# Shield.net
KiCad netlist of a schematic drawn in EAGLE
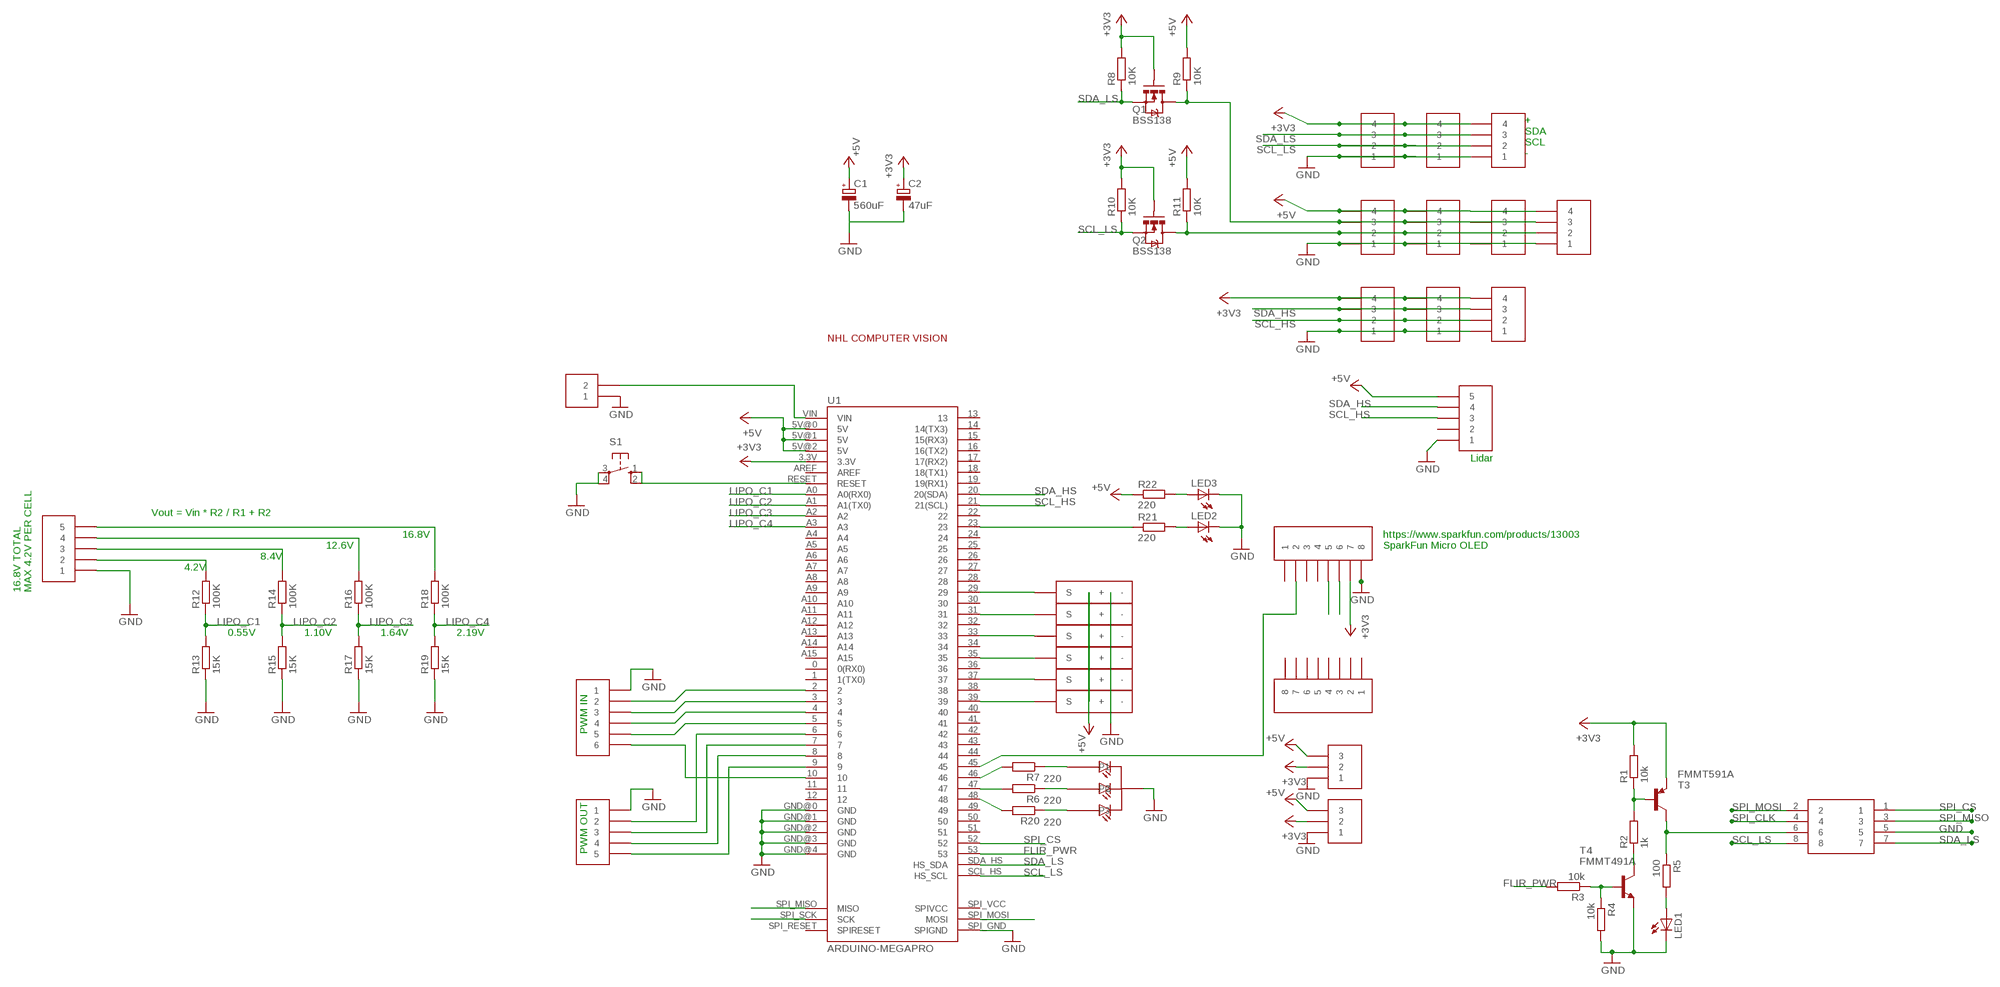
[diagram p0: schematic, sheet 1]

(export (version "E")
  (design (tool "Eeschema 10.0.6"))
  (components
    (comp (ref "C1")
      (value "560uF")
      (footprint "eagle-import:153CLV-1010")
      (libsource (lib "eagle-import") (part "CPOL-EU153CLV-1010"))
    )
    (comp (ref "C2")
      (value "47uF")
      (footprint "eagle-import:153CLV-0605")
      (libsource (lib "eagle-import") (part "CPOL-EU153CLV-0605"))
    )
    (comp (ref "LED1")
      (value "LEDSML0805")
      (footprint "eagle-import:SML0805")
      (libsource (lib "eagle-import") (part "LEDSML0805"))
    )
    (comp (ref "LED2")
      (value "LEDSML0805")
      (footprint "eagle-import:SML0805")
      (libsource (lib "eagle-import") (part "LEDSML0805"))
    )
    (comp (ref "LED3")
      (value "LEDSML0805")
      (footprint "eagle-import:SML0805")
      (libsource (lib "eagle-import") (part "LEDSML0805"))
    )
    (comp (ref "Q1")
      (value "BSS138")
      (footprint "eagle-import:SOT23-3")
      (libsource (lib "eagle-import") (part "MOSFET-NCHANNELBSS138"))
    )
    (comp (ref "Q2")
      (value "BSS138")
      (footprint "eagle-import:SOT23-3")
      (libsource (lib "eagle-import") (part "MOSFET-NCHANNELBSS138"))
    )
    (comp (ref "R1")
      (value "10k")
      (footprint "eagle-import:R0805")
      (libsource (lib "eagle-import") (part "R-EU_R0805"))
    )
    (comp (ref "R2")
      (value "1k")
      (footprint "eagle-import:R0805")
      (libsource (lib "eagle-import") (part "R-EU_R0805"))
    )
    (comp (ref "R3")
      (value "10k")
      (footprint "eagle-import:R0805")
      (libsource (lib "eagle-import") (part "R-EU_R0805"))
    )
    (comp (ref "R4")
      (value "10k")
      (footprint "eagle-import:R0805")
      (libsource (lib "eagle-import") (part "R-EU_R0805"))
    )
    (comp (ref "R5")
      (value "100")
      (footprint "eagle-import:R0805")
      (libsource (lib "eagle-import") (part "R-EU_R0805"))
    )
    (comp (ref "R6")
      (value "220")
      (footprint "eagle-import:R0805")
      (libsource (lib "eagle-import") (part "R-EU_R0805"))
    )
    (comp (ref "R7")
      (value "220")
      (footprint "eagle-import:R0805")
      (libsource (lib "eagle-import") (part "R-EU_R0805"))
    )
    (comp (ref "R8")
      (value "10K")
      (footprint "eagle-import:R0805")
      (libsource (lib "eagle-import") (part "R-EU_R0805"))
    )
    (comp (ref "R9")
      (value "10K")
      (footprint "eagle-import:R0805")
      (libsource (lib "eagle-import") (part "R-EU_R0805"))
    )
    (comp (ref "R10")
      (value "10K")
      (footprint "eagle-import:R0805")
      (libsource (lib "eagle-import") (part "R-EU_R0805"))
    )
    (comp (ref "R11")
      (value "10K")
      (footprint "eagle-import:R0805")
      (libsource (lib "eagle-import") (part "R-EU_R0805"))
    )
    (comp (ref "R12")
      (value "100K")
      (footprint "eagle-import:R0805")
      (libsource (lib "eagle-import") (part "R-EU_R0805"))
    )
    (comp (ref "R13")
      (value "15K")
      (footprint "eagle-import:R0805")
      (libsource (lib "eagle-import") (part "R-EU_R0805"))
    )
    (comp (ref "R14")
      (value "100K")
      (footprint "eagle-import:R0805")
      (libsource (lib "eagle-import") (part "R-EU_R0805"))
    )
    (comp (ref "R15")
      (value "15K")
      (footprint "eagle-import:R0805")
      (libsource (lib "eagle-import") (part "R-EU_R0805"))
    )
    (comp (ref "R16")
      (value "100K")
      (footprint "eagle-import:R0805")
      (libsource (lib "eagle-import") (part "R-EU_R0805"))
    )
    (comp (ref "R17")
      (value "15K")
      (footprint "eagle-import:R0805")
      (libsource (lib "eagle-import") (part "R-EU_R0805"))
    )
    (comp (ref "R18")
      (value "100K")
      (footprint "eagle-import:R0805")
      (libsource (lib "eagle-import") (part "R-EU_R0805"))
    )
    (comp (ref "R19")
      (value "15K")
      (footprint "eagle-import:R0805")
      (libsource (lib "eagle-import") (part "R-EU_R0805"))
    )
    (comp (ref "R20")
      (value "220")
      (footprint "eagle-import:R0805")
      (libsource (lib "eagle-import") (part "R-EU_R0805"))
    )
    (comp (ref "R21")
      (value "220")
      (footprint "eagle-import:R0805")
      (libsource (lib "eagle-import") (part "R-EU_R0805"))
    )
    (comp (ref "R22")
      (value "220")
      (footprint "eagle-import:R0805")
      (libsource (lib "eagle-import") (part "R-EU_R0805"))
    )
    (comp (ref "S1")
      (value "10-XX")
      (footprint "eagle-import:B3F-10XX")
      (fields (field (name "MPN") "B3F-1000"))
      (libsource (lib "eagle-import") (part "10-XX"))
    )
    (comp (ref "T3")
      (value "FMMT591A ")
      (footprint "eagle-import:SOT23-BCE")
      (libsource (lib "eagle-import") (part "-PNP-SOT23-BCE"))
    )
    (comp (ref "T4")
      (value "FMMT491A ")
      (footprint "eagle-import:SOT23-BEC")
      (libsource (lib "eagle-import") (part "-NPN-SOT23-BECBC808"))
    )
    (comp (ref "U$1")
      (value "RGB5MMRGB5MM")
      (footprint "eagle-import:RGB5MM")
      (libsource (lib "eagle-import") (part "RGB5MMRGB5MM"))
    )
    (comp (ref "U$2")
      (value "JST-4")
      (footprint "eagle-import:JST-4")
      (libsource (lib "eagle-import") (part "JST-4"))
    )
    (comp (ref "U$3")
      (value "JST-4")
      (footprint "eagle-import:JST-4")
      (libsource (lib "eagle-import") (part "JST-4"))
    )
    (comp (ref "U$4")
      (value "JST-4")
      (footprint "eagle-import:JST-4")
      (libsource (lib "eagle-import") (part "JST-4"))
    )
    (comp (ref "U$5")
      (value "JST-4")
      (footprint "eagle-import:JST-4")
      (libsource (lib "eagle-import") (part "JST-4"))
    )
    (comp (ref "U$6")
      (value "JST-4")
      (footprint "eagle-import:JST-4")
      (libsource (lib "eagle-import") (part "JST-4"))
    )
    (comp (ref "U$7")
      (value "JST-4")
      (footprint "eagle-import:JST-4")
      (libsource (lib "eagle-import") (part "JST-4"))
    )
    (comp (ref "U$8")
      (value "JST-4")
      (footprint "eagle-import:JST-4")
      (libsource (lib "eagle-import") (part "JST-4"))
    )
    (comp (ref "U$9")
      (value "JST-4")
      (footprint "eagle-import:JST-4")
      (libsource (lib "eagle-import") (part "JST-4"))
    )
    (comp (ref "U$10")
      (value "JST-4")
      (footprint "eagle-import:JST-4")
      (libsource (lib "eagle-import") (part "JST-4"))
    )
    (comp (ref "U$11")
      (value "JST-4")
      (footprint "eagle-import:JST-4")
      (libsource (lib "eagle-import") (part "JST-4"))
    )
    (comp (ref "U$12")
      (value "LIDAR")
      (footprint "eagle-import:JST-5")
      (libsource (lib "eagle-import") (part "JST-5"))
    )
    (comp (ref "U$13")
      (value "LIDAR")
      (footprint "eagle-import:JST-5")
      (libsource (lib "eagle-import") (part "JST-5"))
    )
    (comp (ref "U$14")
      (value "JST-3")
      (footprint "eagle-import:JST-3")
      (libsource (lib "eagle-import") (part "JST-3"))
    )
    (comp (ref "U$15")
      (value "JST-3")
      (footprint "eagle-import:JST-3")
      (libsource (lib "eagle-import") (part "JST-3"))
    )
    (comp (ref "U$16")
      (value "JST-2")
      (footprint "eagle-import:JST-2")
      (libsource (lib "eagle-import") (part "JST-2"))
    )
    (comp (ref "U$17")
      (value "JST-6")
      (footprint "eagle-import:JST-6")
      (libsource (lib "eagle-import") (part "JST-6"))
    )
    (comp (ref "U$18")
      (value "JST-5")
      (footprint "eagle-import:JST-5")
      (libsource (lib "eagle-import") (part "JST-5"))
    )
    (comp (ref "U$19")
      (value "SERVOHEADER")
      (footprint "eagle-import:SERVOHEADER")
      (libsource (lib "eagle-import") (part "SERVOHEADER"))
    )
    (comp (ref "U$20")
      (value "SERVOHEADER")
      (footprint "eagle-import:SERVOHEADER")
      (libsource (lib "eagle-import") (part "SERVOHEADER"))
    )
    (comp (ref "U$21")
      (value "SERVOHEADER")
      (footprint "eagle-import:SERVOHEADER")
      (libsource (lib "eagle-import") (part "SERVOHEADER"))
    )
    (comp (ref "U$22")
      (value "SERVOHEADER")
      (footprint "eagle-import:SERVOHEADER")
      (libsource (lib "eagle-import") (part "SERVOHEADER"))
    )
    (comp (ref "U$23")
      (value "SERVOHEADER")
      (footprint "eagle-import:SERVOHEADER")
      (libsource (lib "eagle-import") (part "SERVOHEADER"))
    )
    (comp (ref "U$24")
      (value "SERVOHEADER")
      (footprint "eagle-import:SERVOHEADER")
      (libsource (lib "eagle-import") (part "SERVOHEADER"))
    )
    (comp (ref "U$25")
      (value "IDC-8WAY")
      (footprint "eagle-import:IDC-8WAY")
      (libsource (lib "eagle-import") (part "IDC-8WAY"))
    )
    (comp (ref "U$26")
      (value "OLEDHEADER")
      (footprint "eagle-import:OLEDHEADER")
      (libsource (lib "eagle-import") (part "OLEDHEADER"))
    )
    (comp (ref "U$27")
      (value "OLEDHEADER")
      (footprint "eagle-import:OLEDHEADER")
      (libsource (lib "eagle-import") (part "OLEDHEADER"))
    )
    (comp (ref "U$28")
      (value "NHLLOGO")
      (footprint "eagle-import:NHLLOGO")
      (libsource (lib "eagle-import") (part "NHLLOGO"))
    )
    (comp (ref "U1")
      (value "ARDUINO-MEGAPRO")
      (footprint "eagle-import:ARDUINO_MEGA-PRO-3.3V")
      (libsource (lib "eagle-import") (part "ARDUINO-MEGAPRO"))
    )
  )
  (nets
    (net (code "1") (name "+3V3") (class "Default")
      (node (ref "C2") (pin "+") (pinfunction "+_+") (pintype "passive"))
      (node (ref "Q1") (pin "1") (pinfunction "G_1") (pintype "passive"))
      (node (ref "Q2") (pin "1") (pinfunction "G_1") (pintype "passive"))
      (node (ref "R1") (pin "2") (pinfunction "2_2") (pintype "passive"))
      (node (ref "R10") (pin "2") (pinfunction "2_2") (pintype "passive"))
      (node (ref "R8") (pin "2") (pinfunction "2_2") (pintype "passive"))
      (node (ref "T3") (pin "E") (pinfunction "E_E") (pintype "passive"))
      (node (ref "U$10") (pin "4") (pinfunction "4_4") (pintype "bidirectional"))
      (node (ref "U$14") (pin "2") (pinfunction "2_2") (pintype "bidirectional"))
      (node (ref "U$15") (pin "2") (pinfunction "2_2") (pintype "bidirectional"))
      (node (ref "U$2") (pin "4") (pinfunction "4_4") (pintype "bidirectional"))
      (node (ref "U$26") (pin "P$7") (pinfunction "7_P$7") (pintype "bidirectional"))
      (node (ref "U$3") (pin "4") (pinfunction "4_4") (pintype "bidirectional"))
      (node (ref "U$4") (pin "4") (pinfunction "4_4") (pintype "bidirectional"))
      (node (ref "U$8") (pin "4") (pinfunction "4_4") (pintype "bidirectional"))
      (node (ref "U$9") (pin "4") (pinfunction "4_4") (pintype "bidirectional"))
      (node (ref "U1") (pin "3.3V") (pinfunction "3.3V_3.3V") (pintype "bidirectional"))
    )
    (net (code "2") (name "+5V") (class "Default")
      (node (ref "C1") (pin "+") (pinfunction "+_+") (pintype "passive"))
      (node (ref "R11") (pin "2") (pinfunction "2_2") (pintype "passive"))
      (node (ref "R22") (pin "1") (pinfunction "1_1") (pintype "passive"))
      (node (ref "R9") (pin "2") (pinfunction "2_2") (pintype "passive"))
      (node (ref "U$11") (pin "4") (pinfunction "4_4") (pintype "bidirectional"))
      (node (ref "U$12") (pin "5") (pinfunction "5_5") (pintype "bidirectional"))
      (node (ref "U$14") (pin "3") (pinfunction "3_3") (pintype "bidirectional"))
      (node (ref "U$15") (pin "3") (pinfunction "3_3") (pintype "bidirectional"))
      (node (ref "U$19") (pin "+") (pinfunction "+_+") (pintype "bidirectional"))
      (node (ref "U$20") (pin "+") (pinfunction "+_+") (pintype "bidirectional"))
      (node (ref "U$21") (pin "+") (pinfunction "+_+") (pintype "bidirectional"))
      (node (ref "U$22") (pin "+") (pinfunction "+_+") (pintype "bidirectional"))
      (node (ref "U$23") (pin "+") (pinfunction "+_+") (pintype "bidirectional"))
      (node (ref "U$24") (pin "+") (pinfunction "+_+") (pintype "bidirectional"))
      (node (ref "U$5") (pin "4") (pinfunction "4_4") (pintype "bidirectional"))
      (node (ref "U$6") (pin "4") (pinfunction "4_4") (pintype "bidirectional"))
      (node (ref "U$7") (pin "4") (pinfunction "4_4") (pintype "bidirectional"))
      (node (ref "U1") (pin "5V@0") (pinfunction "5V_5V@0") (pintype "bidirectional"))
      (node (ref "U1") (pin "5V@1") (pinfunction "5V_5V@1") (pintype "bidirectional"))
      (node (ref "U1") (pin "5V@2") (pinfunction "5V_5V@2") (pintype "bidirectional"))
    )
    (net (code "3") (name "/FLIR_PWR") (class "Default")
      (node (ref "R3") (pin "2") (pinfunction "2_2") (pintype "passive"))
      (node (ref "U1") (pin "53") (pinfunction "53_53") (pintype "bidirectional"))
    )
    (net (code "4") (name "/LIPO_C1") (class "Default")
      (node (ref "R12") (pin "1") (pinfunction "1_1") (pintype "passive"))
      (node (ref "R13") (pin "2") (pinfunction "2_2") (pintype "passive"))
      (node (ref "U1") (pin "A0") (pinfunction "A0(RX0)_A0") (pintype "bidirectional"))
    )
    (net (code "5") (name "/LIPO_C2") (class "Default")
      (node (ref "R14") (pin "1") (pinfunction "1_1") (pintype "passive"))
      (node (ref "R15") (pin "2") (pinfunction "2_2") (pintype "passive"))
      (node (ref "U1") (pin "A1") (pinfunction "A1(TX0)_A1") (pintype "bidirectional"))
    )
    (net (code "6") (name "/LIPO_C3") (class "Default")
      (node (ref "R16") (pin "1") (pinfunction "1_1") (pintype "passive"))
      (node (ref "R17") (pin "2") (pinfunction "2_2") (pintype "passive"))
      (node (ref "U1") (pin "A2") (pinfunction "A2_A2") (pintype "bidirectional"))
    )
    (net (code "7") (name "/LIPO_C4") (class "Default")
      (node (ref "R18") (pin "1") (pinfunction "1_1") (pintype "passive"))
      (node (ref "R19") (pin "2") (pinfunction "2_2") (pintype "passive"))
      (node (ref "U1") (pin "A3") (pinfunction "A3_A3") (pintype "bidirectional"))
    )
    (net (code "8") (name "/SCL_HS") (class "Default")
      (node (ref "U$10") (pin "2") (pinfunction "2_2") (pintype "bidirectional"))
      (node (ref "U$12") (pin "3") (pinfunction "3_3") (pintype "bidirectional"))
      (node (ref "U$8") (pin "2") (pinfunction "2_2") (pintype "bidirectional"))
      (node (ref "U$9") (pin "2") (pinfunction "2_2") (pintype "bidirectional"))
      (node (ref "U1") (pin "21") (pinfunction "21(SCL)_21") (pintype "bidirectional"))
    )
    (net (code "9") (name "/SCL_LS") (class "Default")
      (node (ref "Q2") (pin "2") (pinfunction "S_2") (pintype "passive"))
      (node (ref "R10") (pin "1") (pinfunction "1_1") (pintype "passive"))
      (node (ref "U$2") (pin "2") (pinfunction "2_2") (pintype "bidirectional"))
      (node (ref "U$25") (pin "8") (pinfunction "8_8") (pintype "bidirectional"))
      (node (ref "U$26") (pin "P$5") (pinfunction "5_P$5") (pintype "bidirectional"))
      (node (ref "U$3") (pin "2") (pinfunction "2_2") (pintype "bidirectional"))
      (node (ref "U$4") (pin "2") (pinfunction "2_2") (pintype "bidirectional"))
      (node (ref "U1") (pin "SCL_HS") (pinfunction "HS_SCL_SCL_HS") (pintype "bidirectional"))
    )
    (net (code "10") (name "/SDA_HS") (class "Default")
      (node (ref "U$10") (pin "3") (pinfunction "3_3") (pintype "bidirectional"))
      (node (ref "U$12") (pin "4") (pinfunction "4_4") (pintype "bidirectional"))
      (node (ref "U$8") (pin "3") (pinfunction "3_3") (pintype "bidirectional"))
      (node (ref "U$9") (pin "3") (pinfunction "3_3") (pintype "bidirectional"))
      (node (ref "U1") (pin "20") (pinfunction "20(SDA)_20") (pintype "bidirectional"))
    )
    (net (code "11") (name "/SDA_LS") (class "Default")
      (node (ref "Q1") (pin "2") (pinfunction "S_2") (pintype "passive"))
      (node (ref "R8") (pin "1") (pinfunction "1_1") (pintype "passive"))
      (node (ref "U$2") (pin "3") (pinfunction "3_3") (pintype "bidirectional"))
      (node (ref "U$25") (pin "7") (pinfunction "7_7") (pintype "bidirectional"))
      (node (ref "U$26") (pin "P$6") (pinfunction "6_P$6") (pintype "bidirectional"))
      (node (ref "U$3") (pin "3") (pinfunction "3_3") (pintype "bidirectional"))
      (node (ref "U$4") (pin "3") (pinfunction "3_3") (pintype "bidirectional"))
      (node (ref "U1") (pin "SDA_HS") (pinfunction "HS_SDA_SDA_HS") (pintype "bidirectional"))
    )
    (net (code "12") (name "/SPI_CLK") (class "Default")
      (node (ref "U$25") (pin "4") (pinfunction "4_4") (pintype "bidirectional"))
      (node (ref "U1") (pin "SPI_SCK") (pinfunction "SCK_SPI_SCK") (pintype "bidirectional"))
    )
    (net (code "13") (name "/SPI_CS") (class "Default")
      (node (ref "U$25") (pin "1") (pinfunction "1_1") (pintype "bidirectional"))
      (node (ref "U1") (pin "52") (pinfunction "52_52") (pintype "bidirectional"))
    )
    (net (code "14") (name "/SPI_MISO") (class "Default")
      (node (ref "U$25") (pin "3") (pinfunction "3_3") (pintype "bidirectional"))
      (node (ref "U1") (pin "SPI_MISO") (pinfunction "MISO_SPI_MISO") (pintype "bidirectional"))
    )
    (net (code "15") (name "/SPI_MOSI") (class "Default")
      (node (ref "U$25") (pin "2") (pinfunction "2_2") (pintype "bidirectional"))
      (node (ref "U1") (pin "SPI_MOSI") (pinfunction "MOSI_SPI_MOSI") (pintype "bidirectional"))
    )
    (net (code "16") (name "GND") (class "Default")
      (node (ref "C1") (pin "-") (pinfunction "-_-") (pintype "passive"))
      (node (ref "C2") (pin "-") (pinfunction "-_-") (pintype "passive"))
      (node (ref "LED1") (pin "C") (pinfunction "C_C") (pintype "passive"))
      (node (ref "LED2") (pin "C") (pinfunction "C_C") (pintype "passive"))
      (node (ref "LED3") (pin "C") (pinfunction "C_C") (pintype "passive"))
      (node (ref "R13") (pin "1") (pinfunction "1_1") (pintype "passive"))
      (node (ref "R15") (pin "1") (pinfunction "1_1") (pintype "passive"))
      (node (ref "R17") (pin "1") (pinfunction "1_1") (pintype "passive"))
      (node (ref "R19") (pin "1") (pinfunction "1_1") (pintype "passive"))
      (node (ref "R4") (pin "2") (pinfunction "2_2") (pintype "passive"))
      (node (ref "S1") (pin "3") (pinfunction "P_3") (pintype "passive"))
      (node (ref "S1") (pin "4") (pinfunction "P1_4") (pintype "passive"))
      (node (ref "T4") (pin "E") (pinfunction "E_E") (pintype "passive"))
      (node (ref "U$1") (pin "C") (pinfunction "C_C") (pintype "bidirectional"))
      (node (ref "U$10") (pin "1") (pinfunction "1_1") (pintype "bidirectional"))
      (node (ref "U$11") (pin "1") (pinfunction "1_1") (pintype "bidirectional"))
      (node (ref "U$12") (pin "1") (pinfunction "1_1") (pintype "bidirectional"))
      (node (ref "U$13") (pin "1") (pinfunction "1_1") (pintype "bidirectional"))
      (node (ref "U$14") (pin "1") (pinfunction "1_1") (pintype "bidirectional"))
      (node (ref "U$15") (pin "1") (pinfunction "1_1") (pintype "bidirectional"))
      (node (ref "U$16") (pin "1") (pinfunction "1_1") (pintype "bidirectional"))
      (node (ref "U$17") (pin "1") (pinfunction "1_1") (pintype "bidirectional"))
      (node (ref "U$18") (pin "1") (pinfunction "1_1") (pintype "bidirectional"))
      (node (ref "U$19") (pin "-") (pinfunction "-_-") (pintype "bidirectional"))
      (node (ref "U$2") (pin "1") (pinfunction "1_1") (pintype "bidirectional"))
      (node (ref "U$20") (pin "-") (pinfunction "-_-") (pintype "bidirectional"))
      (node (ref "U$21") (pin "-") (pinfunction "-_-") (pintype "bidirectional"))
      (node (ref "U$22") (pin "-") (pinfunction "-_-") (pintype "bidirectional"))
      (node (ref "U$23") (pin "-") (pinfunction "-_-") (pintype "bidirectional"))
      (node (ref "U$24") (pin "-") (pinfunction "-_-") (pintype "bidirectional"))
      (node (ref "U$25") (pin "5") (pinfunction "5_5") (pintype "bidirectional"))
      (node (ref "U$26") (pin "P$8") (pinfunction "8_P$8") (pintype "bidirectional"))
      (node (ref "U$3") (pin "1") (pinfunction "1_1") (pintype "bidirectional"))
      (node (ref "U$4") (pin "1") (pinfunction "1_1") (pintype "bidirectional"))
      (node (ref "U$5") (pin "1") (pinfunction "1_1") (pintype "bidirectional"))
      (node (ref "U$6") (pin "1") (pinfunction "1_1") (pintype "bidirectional"))
      (node (ref "U$7") (pin "1") (pinfunction "1_1") (pintype "bidirectional"))
      (node (ref "U$8") (pin "1") (pinfunction "1_1") (pintype "bidirectional"))
      (node (ref "U$9") (pin "1") (pinfunction "1_1") (pintype "bidirectional"))
      (node (ref "U1") (pin "GND@0") (pinfunction "GND_GND@0") (pintype "bidirectional"))
      (node (ref "U1") (pin "GND@1") (pinfunction "GND_GND@1") (pintype "bidirectional"))
      (node (ref "U1") (pin "GND@2") (pinfunction "GND_GND@2") (pintype "bidirectional"))
      (node (ref "U1") (pin "GND@3") (pinfunction "GND_GND@3") (pintype "bidirectional"))
      (node (ref "U1") (pin "GND@4") (pinfunction "GND_GND@4") (pintype "bidirectional"))
      (node (ref "U1") (pin "SPI_GND") (pinfunction "SPIGND_SPI_GND") (pintype "bidirectional"))
    )
    (net (code "17") (name "Net-(LED1-PadA)") (class "Default")
      (node (ref "LED1") (pin "A") (pinfunction "A_A") (pintype "passive"))
      (node (ref "R5") (pin "2") (pinfunction "2_2") (pintype "passive"))
    )
    (net (code "18") (name "Net-(LED2-PadA)") (class "Default")
      (node (ref "LED2") (pin "A") (pinfunction "A_A") (pintype "passive"))
      (node (ref "R21") (pin "2") (pinfunction "2_2") (pintype "passive"))
    )
    (net (code "19") (name "Net-(LED3-PadA)") (class "Default")
      (node (ref "LED3") (pin "A") (pinfunction "A_A") (pintype "passive"))
      (node (ref "R22") (pin "2") (pinfunction "2_2") (pintype "passive"))
    )
    (net (code "20") (name "Net-(Q1-D)") (class "Default")
      (node (ref "Q1") (pin "3") (pinfunction "D_3") (pintype "passive"))
      (node (ref "R9") (pin "1") (pinfunction "1_1") (pintype "passive"))
      (node (ref "U$11") (pin "3") (pinfunction "3_3") (pintype "bidirectional"))
      (node (ref "U$5") (pin "3") (pinfunction "3_3") (pintype "bidirectional"))
      (node (ref "U$6") (pin "3") (pinfunction "3_3") (pintype "bidirectional"))
      (node (ref "U$7") (pin "3") (pinfunction "3_3") (pintype "bidirectional"))
    )
    (net (code "21") (name "Net-(Q2-D)") (class "Default")
      (node (ref "Q2") (pin "3") (pinfunction "D_3") (pintype "passive"))
      (node (ref "R11") (pin "1") (pinfunction "1_1") (pintype "passive"))
      (node (ref "U$11") (pin "2") (pinfunction "2_2") (pintype "bidirectional"))
      (node (ref "U$5") (pin "2") (pinfunction "2_2") (pintype "bidirectional"))
      (node (ref "U$6") (pin "2") (pinfunction "2_2") (pintype "bidirectional"))
      (node (ref "U$7") (pin "2") (pinfunction "2_2") (pintype "bidirectional"))
    )
    (net (code "22") (name "Net-(R1-Pad1)") (class "Default")
      (node (ref "R1") (pin "1") (pinfunction "1_1") (pintype "passive"))
      (node (ref "R2") (pin "2") (pinfunction "2_2") (pintype "passive"))
      (node (ref "T3") (pin "B") (pinfunction "B_B") (pintype "passive"))
    )
    (net (code "23") (name "Net-(R2-Pad1)") (class "Default")
      (node (ref "R2") (pin "1") (pinfunction "1_1") (pintype "passive"))
      (node (ref "T4") (pin "C") (pinfunction "C_C") (pintype "passive"))
    )
    (net (code "24") (name "Net-(R3-Pad1)") (class "Default")
      (node (ref "R3") (pin "1") (pinfunction "1_1") (pintype "passive"))
      (node (ref "R4") (pin "1") (pinfunction "1_1") (pintype "passive"))
      (node (ref "T4") (pin "B") (pinfunction "B_B") (pintype "passive"))
    )
    (net (code "25") (name "Net-(R5-Pad1)") (class "Default")
      (node (ref "R5") (pin "1") (pinfunction "1_1") (pintype "passive"))
      (node (ref "T3") (pin "C") (pinfunction "C_C") (pintype "passive"))
      (node (ref "U$25") (pin "6") (pinfunction "6_6") (pintype "bidirectional"))
    )
    (net (code "26") (name "Net-(R6-Pad1)") (class "Default")
      (node (ref "R6") (pin "1") (pinfunction "1_1") (pintype "passive"))
      (node (ref "U$1") (pin "P2") (pinfunction "P2_P2") (pintype "bidirectional"))
    )
    (net (code "27") (name "Net-(R6-Pad2)") (class "Default")
      (node (ref "R6") (pin "2") (pinfunction "2_2") (pintype "passive"))
      (node (ref "U1") (pin "47") (pinfunction "47_47") (pintype "bidirectional"))
    )
    (net (code "28") (name "Net-(R7-Pad1)") (class "Default")
      (node (ref "R7") (pin "1") (pinfunction "1_1") (pintype "passive"))
      (node (ref "U$1") (pin "P1") (pinfunction "P1_P1") (pintype "bidirectional"))
    )
    (net (code "29") (name "Net-(R7-Pad2)") (class "Default")
      (node (ref "R7") (pin "2") (pinfunction "2_2") (pintype "passive"))
      (node (ref "U1") (pin "46") (pinfunction "46_46") (pintype "bidirectional"))
    )
    (net (code "30") (name "Net-(R12-Pad2)") (class "Default")
      (node (ref "R12") (pin "2") (pinfunction "2_2") (pintype "passive"))
      (node (ref "U$13") (pin "2") (pinfunction "2_2") (pintype "bidirectional"))
    )
    (net (code "31") (name "Net-(R14-Pad2)") (class "Default")
      (node (ref "R14") (pin "2") (pinfunction "2_2") (pintype "passive"))
      (node (ref "U$13") (pin "3") (pinfunction "3_3") (pintype "bidirectional"))
    )
    (net (code "32") (name "Net-(R16-Pad2)") (class "Default")
      (node (ref "R16") (pin "2") (pinfunction "2_2") (pintype "passive"))
      (node (ref "U$13") (pin "4") (pinfunction "4_4") (pintype "bidirectional"))
    )
    (net (code "33") (name "Net-(R18-Pad2)") (class "Default")
      (node (ref "R18") (pin "2") (pinfunction "2_2") (pintype "passive"))
      (node (ref "U$13") (pin "5") (pinfunction "5_5") (pintype "bidirectional"))
    )
    (net (code "34") (name "Net-(R20-Pad1)") (class "Default")
      (node (ref "R20") (pin "1") (pinfunction "1_1") (pintype "passive"))
      (node (ref "U$1") (pin "P3") (pinfunction "P3_P3") (pintype "bidirectional"))
    )
    (net (code "35") (name "Net-(R20-Pad2)") (class "Default")
      (node (ref "R20") (pin "2") (pinfunction "2_2") (pintype "passive"))
      (node (ref "U1") (pin "48") (pinfunction "48_48") (pintype "bidirectional"))
    )
    (net (code "36") (name "Net-(R21-Pad1)") (class "Default")
      (node (ref "R21") (pin "1") (pinfunction "1_1") (pintype "passive"))
      (node (ref "U1") (pin "23") (pinfunction "23_23") (pintype "bidirectional"))
    )
    (net (code "37") (name "Net-(S1-S)") (class "Default")
      (node (ref "S1") (pin "1") (pinfunction "S_1") (pintype "passive"))
      (node (ref "S1") (pin "2") (pinfunction "S1_2") (pintype "passive"))
      (node (ref "U1") (pin "RESET") (pinfunction "RESET_RESET") (pintype "bidirectional"))
    )
    (net (code "38") (name "Net-(U$16-Pad2)") (class "Default")
      (node (ref "U$16") (pin "2") (pinfunction "2_2") (pintype "bidirectional"))
      (node (ref "U1") (pin "VIN") (pinfunction "VIN_VIN") (pintype "bidirectional"))
    )
    (net (code "39") (name "Net-(U$17-Pad2)") (class "Default")
      (node (ref "U$17") (pin "2") (pinfunction "2_2") (pintype "bidirectional"))
      (node (ref "U1") (pin "2") (pinfunction "2_2") (pintype "bidirectional"))
    )
    (net (code "40") (name "Net-(U$17-Pad3)") (class "Default")
      (node (ref "U$17") (pin "3") (pinfunction "3_3") (pintype "bidirectional"))
      (node (ref "U1") (pin "3") (pinfunction "3_3") (pintype "bidirectional"))
    )
    (net (code "41") (name "Net-(U$17-Pad4)") (class "Default")
      (node (ref "U$17") (pin "4") (pinfunction "4_4") (pintype "bidirectional"))
      (node (ref "U1") (pin "4") (pinfunction "4_4") (pintype "bidirectional"))
    )
    (net (code "42") (name "Net-(U$17-Pad5)") (class "Default")
      (node (ref "U$17") (pin "5") (pinfunction "5_5") (pintype "bidirectional"))
      (node (ref "U1") (pin "5") (pinfunction "5_5") (pintype "bidirectional"))
    )
    (net (code "43") (name "Net-(U$17-Pad6)") (class "Default")
      (node (ref "U$17") (pin "6") (pinfunction "6_6") (pintype "bidirectional"))
      (node (ref "U1") (pin "10") (pinfunction "10_10") (pintype "bidirectional"))
    )
    (net (code "44") (name "Net-(U$18-Pad2)") (class "Default")
      (node (ref "U$18") (pin "2") (pinfunction "2_2") (pintype "bidirectional"))
      (node (ref "U1") (pin "6") (pinfunction "6_6") (pintype "bidirectional"))
    )
    (net (code "45") (name "Net-(U$18-Pad3)") (class "Default")
      (node (ref "U$18") (pin "3") (pinfunction "3_3") (pintype "bidirectional"))
      (node (ref "U1") (pin "7") (pinfunction "7_7") (pintype "bidirectional"))
    )
    (net (code "46") (name "Net-(U$18-Pad4)") (class "Default")
      (node (ref "U$18") (pin "4") (pinfunction "4_4") (pintype "bidirectional"))
      (node (ref "U1") (pin "8") (pinfunction "8_8") (pintype "bidirectional"))
    )
    (net (code "47") (name "Net-(U$18-Pad5)") (class "Default")
      (node (ref "U$18") (pin "5") (pinfunction "5_5") (pintype "bidirectional"))
      (node (ref "U1") (pin "9") (pinfunction "9_9") (pintype "bidirectional"))
    )
    (net (code "48") (name "Net-(U$19-PadS)") (class "Default")
      (node (ref "U$19") (pin "S") (pinfunction "S_S") (pintype "bidirectional"))
      (node (ref "U1") (pin "39") (pinfunction "39_39") (pintype "bidirectional"))
    )
    (net (code "49") (name "Net-(U$20-PadS)") (class "Default")
      (node (ref "U$20") (pin "S") (pinfunction "S_S") (pintype "bidirectional"))
      (node (ref "U1") (pin "37") (pinfunction "37_37") (pintype "bidirectional"))
    )
    (net (code "50") (name "Net-(U$21-PadS)") (class "Default")
      (node (ref "U$21") (pin "S") (pinfunction "S_S") (pintype "bidirectional"))
      (node (ref "U1") (pin "35") (pinfunction "35_35") (pintype "bidirectional"))
    )
    (net (code "51") (name "Net-(U$22-PadS)") (class "Default")
      (node (ref "U$22") (pin "S") (pinfunction "S_S") (pintype "bidirectional"))
      (node (ref "U1") (pin "33") (pinfunction "33_33") (pintype "bidirectional"))
    )
    (net (code "52") (name "Net-(U$23-PadS)") (class "Default")
      (node (ref "U$23") (pin "S") (pinfunction "S_S") (pintype "bidirectional"))
      (node (ref "U1") (pin "31") (pinfunction "31_31") (pintype "bidirectional"))
    )
    (net (code "53") (name "Net-(U$24-PadS)") (class "Default")
      (node (ref "U$24") (pin "S") (pinfunction "S_S") (pintype "bidirectional"))
      (node (ref "U1") (pin "29") (pinfunction "29_29") (pintype "bidirectional"))
    )
    (net (code "54") (name "Net-(U$26-2)") (class "Default")
      (node (ref "U$26") (pin "P$2") (pinfunction "2_P$2") (pintype "bidirectional"))
      (node (ref "U1") (pin "45") (pinfunction "45_45") (pintype "bidirectional"))
    )
    (net (code "55") (name "unconnected-(U$12-Pad2)") (class "Default")
      (node (ref "U$12") (pin "2") (pinfunction "2_2") (pintype "bidirectional"))
    )
    (net (code "56") (name "unconnected-(U$26-1-PadP$1)") (class "Default")
      (node (ref "U$26") (pin "P$1") (pinfunction "1_P$1") (pintype "bidirectional"))
    )
    (net (code "57") (name "unconnected-(U$26-3-PadP$3)") (class "Default")
      (node (ref "U$26") (pin "P$3") (pinfunction "3_P$3") (pintype "bidirectional"))
    )
    (net (code "58") (name "unconnected-(U$26-4-PadP$4)") (class "Default")
      (node (ref "U$26") (pin "P$4") (pinfunction "4_P$4") (pintype "bidirectional"))
    )
    (net (code "59") (name "unconnected-(U$27-1-PadP$1)") (class "Default")
      (node (ref "U$27") (pin "P$1") (pinfunction "1_P$1") (pintype "bidirectional"))
    )
    (net (code "60") (name "unconnected-(U$27-2-PadP$2)") (class "Default")
      (node (ref "U$27") (pin "P$2") (pinfunction "2_P$2") (pintype "bidirectional"))
    )
    (net (code "61") (name "unconnected-(U$27-3-PadP$3)") (class "Default")
      (node (ref "U$27") (pin "P$3") (pinfunction "3_P$3") (pintype "bidirectional"))
    )
    (net (code "62") (name "unconnected-(U$27-4-PadP$4)") (class "Default")
      (node (ref "U$27") (pin "P$4") (pinfunction "4_P$4") (pintype "bidirectional"))
    )
    (net (code "63") (name "unconnected-(U$27-5-PadP$5)") (class "Default")
      (node (ref "U$27") (pin "P$5") (pinfunction "5_P$5") (pintype "bidirectional"))
    )
    (net (code "64") (name "unconnected-(U$27-6-PadP$6)") (class "Default")
      (node (ref "U$27") (pin "P$6") (pinfunction "6_P$6") (pintype "bidirectional"))
    )
    (net (code "65") (name "unconnected-(U$27-7-PadP$7)") (class "Default")
      (node (ref "U$27") (pin "P$7") (pinfunction "7_P$7") (pintype "bidirectional"))
    )
    (net (code "66") (name "unconnected-(U$27-8-PadP$8)") (class "Default")
      (node (ref "U$27") (pin "P$8") (pinfunction "8_P$8") (pintype "bidirectional"))
    )
    (net (code "67") (name "unconnected-(U1-0(RX0)-Pad0)") (class "Default")
      (node (ref "U1") (pin "0") (pinfunction "0(RX0)_0") (pintype "bidirectional"))
    )
    (net (code "68") (name "unconnected-(U1-1(TX0)-Pad1)") (class "Default")
      (node (ref "U1") (pin "1") (pinfunction "1(TX0)_1") (pintype "bidirectional"))
    )
    (net (code "69") (name "unconnected-(U1-14(TX3)-Pad14)") (class "Default")
      (node (ref "U1") (pin "14") (pinfunction "14(TX3)_14") (pintype "bidirectional"))
    )
    (net (code "70") (name "unconnected-(U1-15(RX3)-Pad15)") (class "Default")
      (node (ref "U1") (pin "15") (pinfunction "15(RX3)_15") (pintype "bidirectional"))
    )
    (net (code "71") (name "unconnected-(U1-16(TX2)-Pad16)") (class "Default")
      (node (ref "U1") (pin "16") (pinfunction "16(TX2)_16") (pintype "bidirectional"))
    )
    (net (code "72") (name "unconnected-(U1-17(RX2)-Pad17)") (class "Default")
      (node (ref "U1") (pin "17") (pinfunction "17(RX2)_17") (pintype "bidirectional"))
    )
    (net (code "73") (name "unconnected-(U1-18(TX1)-Pad18)") (class "Default")
      (node (ref "U1") (pin "18") (pinfunction "18(TX1)_18") (pintype "bidirectional"))
    )
    (net (code "74") (name "unconnected-(U1-19(RX1)-Pad19)") (class "Default")
      (node (ref "U1") (pin "19") (pinfunction "19(RX1)_19") (pintype "bidirectional"))
    )
    (net (code "75") (name "unconnected-(U1-Pad11)") (class "Default")
      (node (ref "U1") (pin "11") (pinfunction "11_11") (pintype "bidirectional"))
    )
    (net (code "76") (name "unconnected-(U1-Pad12)") (class "Default")
      (node (ref "U1") (pin "12") (pinfunction "12_12") (pintype "bidirectional"))
    )
    (net (code "77") (name "unconnected-(U1-Pad13)") (class "Default")
      (node (ref "U1") (pin "13") (pinfunction "13_13") (pintype "bidirectional"))
    )
    (net (code "78") (name "unconnected-(U1-Pad22)") (class "Default")
      (node (ref "U1") (pin "22") (pinfunction "22_22") (pintype "bidirectional"))
    )
    (net (code "79") (name "unconnected-(U1-Pad24)") (class "Default")
      (node (ref "U1") (pin "24") (pinfunction "24_24") (pintype "bidirectional"))
    )
    (net (code "80") (name "unconnected-(U1-Pad25)") (class "Default")
      (node (ref "U1") (pin "25") (pinfunction "25_25") (pintype "bidirectional"))
    )
    (net (code "81") (name "unconnected-(U1-Pad26)") (class "Default")
      (node (ref "U1") (pin "26") (pinfunction "26_26") (pintype "bidirectional"))
    )
    (net (code "82") (name "unconnected-(U1-Pad27)") (class "Default")
      (node (ref "U1") (pin "27") (pinfunction "27_27") (pintype "bidirectional"))
    )
    (net (code "83") (name "unconnected-(U1-Pad28)") (class "Default")
      (node (ref "U1") (pin "28") (pinfunction "28_28") (pintype "bidirectional"))
    )
    (net (code "84") (name "unconnected-(U1-Pad30)") (class "Default")
      (node (ref "U1") (pin "30") (pinfunction "30_30") (pintype "bidirectional"))
    )
    (net (code "85") (name "unconnected-(U1-Pad32)") (class "Default")
      (node (ref "U1") (pin "32") (pinfunction "32_32") (pintype "bidirectional"))
    )
    (net (code "86") (name "unconnected-(U1-Pad34)") (class "Default")
      (node (ref "U1") (pin "34") (pinfunction "34_34") (pintype "bidirectional"))
    )
    (net (code "87") (name "unconnected-(U1-Pad36)") (class "Default")
      (node (ref "U1") (pin "36") (pinfunction "36_36") (pintype "bidirectional"))
    )
    (net (code "88") (name "unconnected-(U1-Pad38)") (class "Default")
      (node (ref "U1") (pin "38") (pinfunction "38_38") (pintype "bidirectional"))
    )
    (net (code "89") (name "unconnected-(U1-Pad40)") (class "Default")
      (node (ref "U1") (pin "40") (pinfunction "40_40") (pintype "bidirectional"))
    )
    (net (code "90") (name "unconnected-(U1-Pad41)") (class "Default")
      (node (ref "U1") (pin "41") (pinfunction "41_41") (pintype "bidirectional"))
    )
    (net (code "91") (name "unconnected-(U1-Pad42)") (class "Default")
      (node (ref "U1") (pin "42") (pinfunction "42_42") (pintype "bidirectional"))
    )
    (net (code "92") (name "unconnected-(U1-Pad43)") (class "Default")
      (node (ref "U1") (pin "43") (pinfunction "43_43") (pintype "bidirectional"))
    )
    (net (code "93") (name "unconnected-(U1-Pad44)") (class "Default")
      (node (ref "U1") (pin "44") (pinfunction "44_44") (pintype "bidirectional"))
    )
    (net (code "94") (name "unconnected-(U1-Pad49)") (class "Default")
      (node (ref "U1") (pin "49") (pinfunction "49_49") (pintype "bidirectional"))
    )
    (net (code "95") (name "unconnected-(U1-Pad50)") (class "Default")
      (node (ref "U1") (pin "50") (pinfunction "50_50") (pintype "bidirectional"))
    )
    (net (code "96") (name "unconnected-(U1-Pad51)") (class "Default")
      (node (ref "U1") (pin "51") (pinfunction "51_51") (pintype "bidirectional"))
    )
    (net (code "97") (name "unconnected-(U1-PadA4)") (class "Default")
      (node (ref "U1") (pin "A4") (pinfunction "A4_A4") (pintype "bidirectional"))
    )
    (net (code "98") (name "unconnected-(U1-PadA5)") (class "Default")
      (node (ref "U1") (pin "A5") (pinfunction "A5_A5") (pintype "bidirectional"))
    )
    (net (code "99") (name "unconnected-(U1-PadA6)") (class "Default")
      (node (ref "U1") (pin "A6") (pinfunction "A6_A6") (pintype "bidirectional"))
    )
    (net (code "100") (name "unconnected-(U1-PadA7)") (class "Default")
      (node (ref "U1") (pin "A7") (pinfunction "A7_A7") (pintype "bidirectional"))
    )
    (net (code "101") (name "unconnected-(U1-PadA8)") (class "Default")
      (node (ref "U1") (pin "A8") (pinfunction "A8_A8") (pintype "bidirectional"))
    )
    (net (code "102") (name "unconnected-(U1-PadA9)") (class "Default")
      (node (ref "U1") (pin "A9") (pinfunction "A9_A9") (pintype "bidirectional"))
    )
    (net (code "103") (name "unconnected-(U1-PadA10)") (class "Default")
      (node (ref "U1") (pin "A10") (pinfunction "A10_A10") (pintype "bidirectional"))
    )
    (net (code "104") (name "unconnected-(U1-PadA11)") (class "Default")
      (node (ref "U1") (pin "A11") (pinfunction "A11_A11") (pintype "bidirectional"))
    )
    (net (code "105") (name "unconnected-(U1-PadA12)") (class "Default")
      (node (ref "U1") (pin "A12") (pinfunction "A12_A12") (pintype "bidirectional"))
    )
    (net (code "106") (name "unconnected-(U1-PadA13)") (class "Default")
      (node (ref "U1") (pin "A13") (pinfunction "A13_A13") (pintype "bidirectional"))
    )
    (net (code "107") (name "unconnected-(U1-PadA14)") (class "Default")
      (node (ref "U1") (pin "A14") (pinfunction "A14_A14") (pintype "bidirectional"))
    )
    (net (code "108") (name "unconnected-(U1-PadA15)") (class "Default")
      (node (ref "U1") (pin "A15") (pinfunction "A15_A15") (pintype "bidirectional"))
    )
    (net (code "109") (name "unconnected-(U1-PadAREF)") (class "Default")
      (node (ref "U1") (pin "AREF") (pinfunction "AREF_AREF") (pintype "bidirectional"))
    )
    (net (code "110") (name "unconnected-(U1-SPIRESET-PadSPI_RESET)") (class "Default")
      (node (ref "U1") (pin "SPI_RESET") (pinfunction "SPIRESET_SPI_RESET") (pintype "bidirectional"))
    )
    (net (code "111") (name "unconnected-(U1-SPIVCC-PadSPI_VCC)") (class "Default")
      (node (ref "U1") (pin "SPI_VCC") (pinfunction "SPIVCC_SPI_VCC") (pintype "bidirectional"))
    )
  )
)
